# Hall_Digital_Sensor.net
KiCad netlist of a schematic drawn in Altium Designer
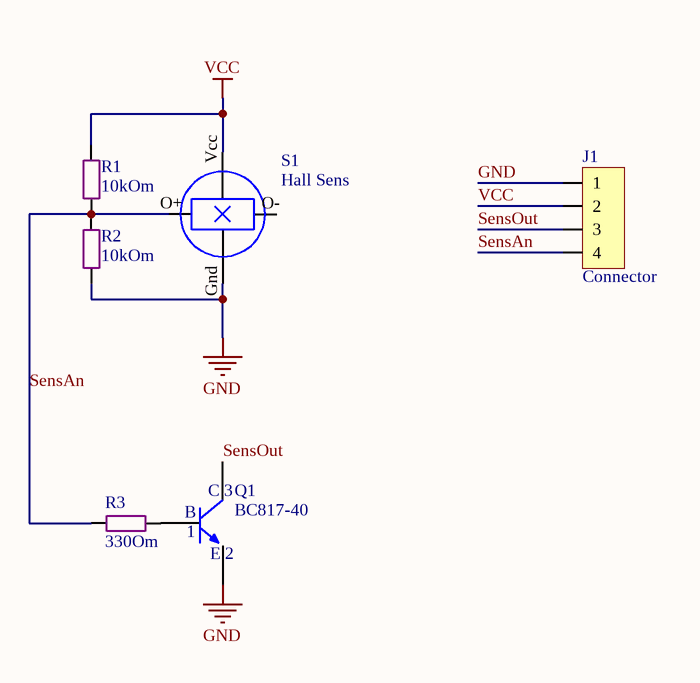
[diagram p0: Hall Digital Sensor.SchDoc]

(export (version "E")
  (design (tool "Eeschema 10.0.6"))
  (components
    (comp (ref "J1")
      (value "Connector")
      (footprint "Connector:Molex Micro-Fit 3.0 - 4 pin D R")
      (description "Horisontal, Dbl line, Male - 3mm")
      (fields (field (name "PART NUMBER") "0430450402"))
      (libsource (lib "Connector") (part "Micro-Fit 4R (2x2)"))
    )
    (comp (ref "Q1")
      (value "BC817-40")
      (footprint "GeneralCases:SOT-23")
      (description "NPN 45 V, 500 mA NPN general-purpose transistor")
      (libsource (lib "Transistor") (part "BC817-40"))
    )
    (comp (ref "R1")
      (value "10kOm")
      (footprint "PassiveComponents:SMD 0805 (2012)")
      (libsource (lib "PassiveComponents") (part "Res All Types"))
    )
    (comp (ref "R2")
      (value "10kOm")
      (footprint "PassiveComponents:SMD 0805 (2012)")
      (libsource (lib "PassiveComponents") (part "Res All Types"))
    )
    (comp (ref "R3")
      (value "330Om")
      (footprint "PassiveComponents:SMD 0805 (2012)")
      (libsource (lib "PassiveComponents") (part "Res All Types"))
    )
    (comp (ref "S1")
      (value "Hall Sens")
      (footprint "Sensors:Hall Sensor 3Pin")
      (libsource (lib "Sensors") (part "Hall Sensor K1116KP8"))
    )
  )
  (nets
    (net (code "1") (name "/SensAn") (class "Default")
      (node (ref "J1") (pin "4") (pinfunction "4_4") (pintype "passive"))
      (node (ref "R1") (pin "1") (pinfunction "1_1") (pintype "passive"))
      (node (ref "R2") (pin "2") (pinfunction "2_2") (pintype "passive"))
      (node (ref "R3") (pin "1") (pinfunction "1_1") (pintype "passive"))
      (node (ref "S1") (pin "O+") (pinfunction "O+_O+") (pintype "passive"))
    )
    (net (code "2") (name "/SensOut") (class "Default")
      (node (ref "J1") (pin "3") (pinfunction "3_3") (pintype "passive"))
      (node (ref "Q1") (pin "3") (pinfunction "C_3") (pintype "passive"))
    )
    (net (code "3") (name "GND") (class "Default")
      (node (ref "J1") (pin "1") (pinfunction "1_1") (pintype "passive"))
      (node (ref "Q1") (pin "2") (pinfunction "E_2") (pintype "passive"))
      (node (ref "R2") (pin "1") (pinfunction "1_1") (pintype "passive"))
      (node (ref "S1") (pin "Gnd") (pinfunction "Gnd_Gnd") (pintype "passive"))
    )
    (net (code "4") (name "Net-(Q1-B)") (class "Default")
      (node (ref "Q1") (pin "1") (pinfunction "B_1") (pintype "passive"))
      (node (ref "R3") (pin "2") (pinfunction "2_2") (pintype "passive"))
    )
    (net (code "5") (name "VCC") (class "Default")
      (node (ref "J1") (pin "2") (pinfunction "2_2") (pintype "passive"))
      (node (ref "R1") (pin "2") (pinfunction "2_2") (pintype "passive"))
      (node (ref "S1") (pin "Vcc") (pinfunction "Vcc_Vcc") (pintype "passive"))
    )
    (net (code "6") (name "unconnected-(S1-PadO-)") (class "Default")
      (node (ref "S1") (pin "O-") (pinfunction "O-_O-") (pintype "passive"))
    )
  )
)
